# S205D.net
KiCad netlist of a schematic drawn in EAGLE
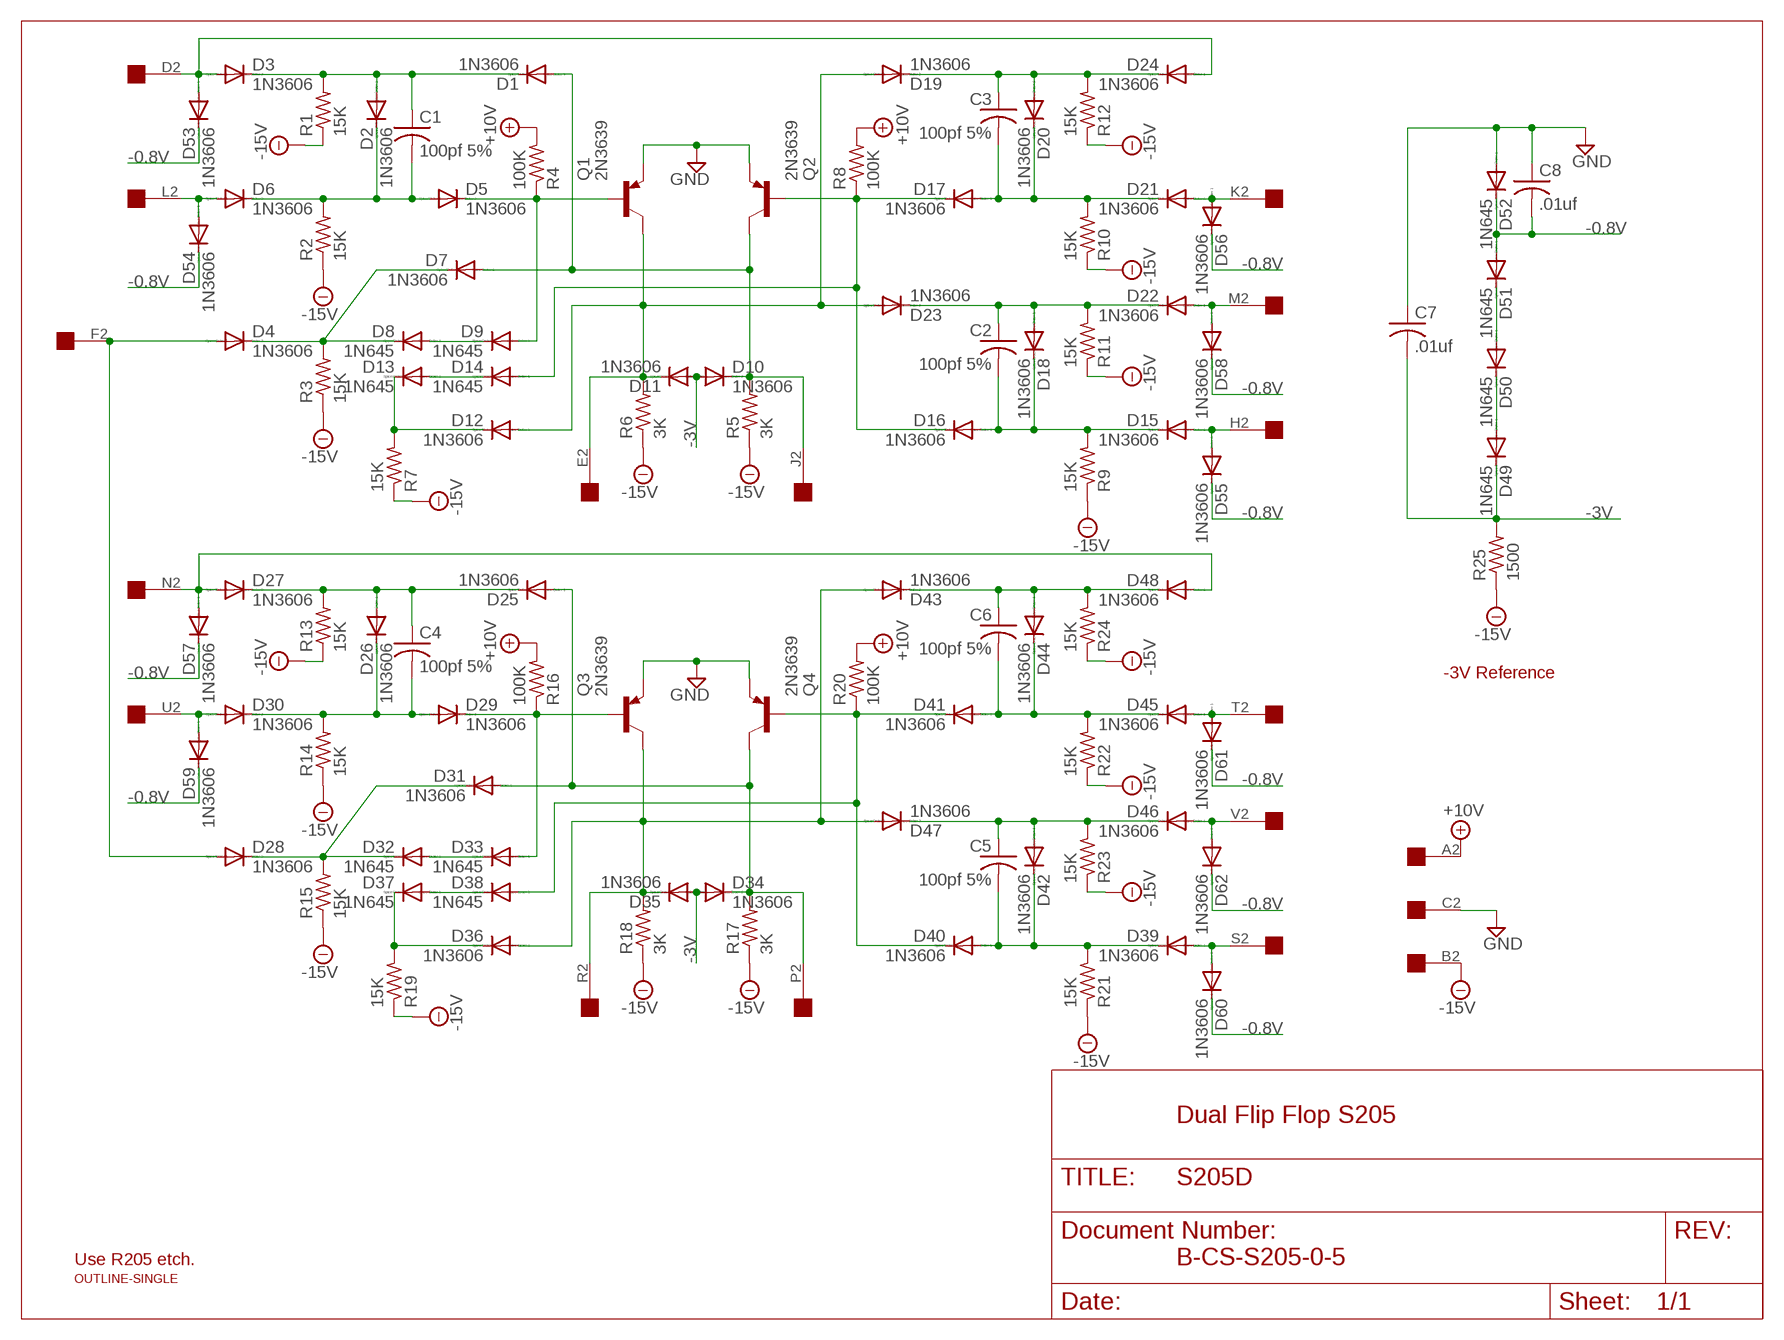
[diagram p0: schematic, sheet 1]

(export (version "E")
  (design (tool "Eeschema 10.0.6"))
  (components
    (comp (ref "C1")
      (value "100pf 5%")
      (footprint "eagle-import:C050-025X075")
      (libsource (lib "eagle-import") (part "C-US050-025X075"))
    )
    (comp (ref "C2")
      (value "100pf 5%")
      (footprint "eagle-import:C050-025X075")
      (libsource (lib "eagle-import") (part "C-US050-025X075"))
    )
    (comp (ref "C3")
      (value "100pf 5%")
      (footprint "eagle-import:C050-025X075")
      (libsource (lib "eagle-import") (part "C-US050-025X075"))
    )
    (comp (ref "C4")
      (value "100pf 5%")
      (footprint "eagle-import:C050-025X075")
      (libsource (lib "eagle-import") (part "C-US050-025X075"))
    )
    (comp (ref "C5")
      (value "100pf 5%")
      (footprint "eagle-import:C050-025X075")
      (libsource (lib "eagle-import") (part "C-US050-025X075"))
    )
    (comp (ref "C6")
      (value "100pf 5%")
      (footprint "eagle-import:C050-025X075")
      (libsource (lib "eagle-import") (part "C-US050-025X075"))
    )
    (comp (ref "C7")
      (value ".01uf")
      (footprint "eagle-import:C050-025X075")
      (libsource (lib "eagle-import") (part "C-US050-025X075"))
    )
    (comp (ref "C8")
      (value ".01uf")
      (footprint "eagle-import:C050-025X075")
      (libsource (lib "eagle-import") (part "C-US050-025X075"))
    )
    (comp (ref "D1")
      (value "1N3606")
      (footprint "eagle-import:DO35-10")
      (libsource (lib "eagle-import") (part "1N4148DO35-10"))
    )
    (comp (ref "D2")
      (value "1N3606")
      (footprint "eagle-import:DO35-10")
      (libsource (lib "eagle-import") (part "1N4148DO35-10"))
    )
    (comp (ref "D3")
      (value "1N3606")
      (footprint "eagle-import:DO35-10")
      (libsource (lib "eagle-import") (part "1N4148DO35-10"))
    )
    (comp (ref "D4")
      (value "1N3606")
      (footprint "eagle-import:DO35-10")
      (libsource (lib "eagle-import") (part "1N4148DO35-10"))
    )
    (comp (ref "D5")
      (value "1N3606")
      (footprint "eagle-import:DO35-10")
      (libsource (lib "eagle-import") (part "1N4148DO35-10"))
    )
    (comp (ref "D6")
      (value "1N3606")
      (footprint "eagle-import:DO35-10")
      (libsource (lib "eagle-import") (part "1N4148DO35-10"))
    )
    (comp (ref "D7")
      (value "1N3606")
      (footprint "eagle-import:DO35-10")
      (libsource (lib "eagle-import") (part "1N4148DO35-10"))
    )
    (comp (ref "D8")
      (value "1N645")
      (footprint "eagle-import:DO35-10")
      (libsource (lib "eagle-import") (part "1N4148DO35-10"))
    )
    (comp (ref "D9")
      (value "1N645")
      (footprint "eagle-import:DO35-10")
      (libsource (lib "eagle-import") (part "1N4148DO35-10"))
    )
    (comp (ref "D10")
      (value "1N3606")
      (footprint "eagle-import:DO35-10")
      (libsource (lib "eagle-import") (part "1N4148DO35-10"))
    )
    (comp (ref "D11")
      (value "1N3606")
      (footprint "eagle-import:DO35-10")
      (libsource (lib "eagle-import") (part "1N4148DO35-10"))
    )
    (comp (ref "D12")
      (value "1N3606")
      (footprint "eagle-import:DO35-10")
      (libsource (lib "eagle-import") (part "1N4148DO35-10"))
    )
    (comp (ref "D13")
      (value "1N645")
      (footprint "eagle-import:DO35-10")
      (libsource (lib "eagle-import") (part "1N4148DO35-10"))
    )
    (comp (ref "D14")
      (value "1N645")
      (footprint "eagle-import:DO35-10")
      (libsource (lib "eagle-import") (part "1N4148DO35-10"))
    )
    (comp (ref "D15")
      (value "1N3606")
      (footprint "eagle-import:DO35-10")
      (libsource (lib "eagle-import") (part "1N4148DO35-10"))
    )
    (comp (ref "D16")
      (value "1N3606")
      (footprint "eagle-import:DO35-10")
      (libsource (lib "eagle-import") (part "1N4148DO35-10"))
    )
    (comp (ref "D17")
      (value "1N3606")
      (footprint "eagle-import:DO35-10")
      (libsource (lib "eagle-import") (part "1N4148DO35-10"))
    )
    (comp (ref "D18")
      (value "1N3606")
      (footprint "eagle-import:DO35-10")
      (libsource (lib "eagle-import") (part "1N4148DO35-10"))
    )
    (comp (ref "D19")
      (value "1N3606")
      (footprint "eagle-import:DO35-10")
      (libsource (lib "eagle-import") (part "1N4148DO35-10"))
    )
    (comp (ref "D20")
      (value "1N3606")
      (footprint "eagle-import:DO35-10")
      (libsource (lib "eagle-import") (part "1N4148DO35-10"))
    )
    (comp (ref "D21")
      (value "1N3606")
      (footprint "eagle-import:DO35-10")
      (libsource (lib "eagle-import") (part "1N4148DO35-10"))
    )
    (comp (ref "D22")
      (value "1N3606")
      (footprint "eagle-import:DO35-10")
      (libsource (lib "eagle-import") (part "1N4148DO35-10"))
    )
    (comp (ref "D23")
      (value "1N3606")
      (footprint "eagle-import:DO35-10")
      (libsource (lib "eagle-import") (part "1N4148DO35-10"))
    )
    (comp (ref "D24")
      (value "1N3606")
      (footprint "eagle-import:DO35-10")
      (libsource (lib "eagle-import") (part "1N4148DO35-10"))
    )
    (comp (ref "D25")
      (value "1N3606")
      (footprint "eagle-import:DO35-10")
      (libsource (lib "eagle-import") (part "1N4148DO35-10"))
    )
    (comp (ref "D26")
      (value "1N3606")
      (footprint "eagle-import:DO35-10")
      (libsource (lib "eagle-import") (part "1N4148DO35-10"))
    )
    (comp (ref "D27")
      (value "1N3606")
      (footprint "eagle-import:DO35-10")
      (libsource (lib "eagle-import") (part "1N4148DO35-10"))
    )
    (comp (ref "D28")
      (value "1N3606")
      (footprint "eagle-import:DO35-10")
      (libsource (lib "eagle-import") (part "1N4148DO35-10"))
    )
    (comp (ref "D29")
      (value "1N3606")
      (footprint "eagle-import:DO35-10")
      (libsource (lib "eagle-import") (part "1N4148DO35-10"))
    )
    (comp (ref "D30")
      (value "1N3606")
      (footprint "eagle-import:DO35-10")
      (libsource (lib "eagle-import") (part "1N4148DO35-10"))
    )
    (comp (ref "D31")
      (value "1N3606")
      (footprint "eagle-import:DO35-10")
      (libsource (lib "eagle-import") (part "1N4148DO35-10"))
    )
    (comp (ref "D32")
      (value "1N645")
      (footprint "eagle-import:DO35-10")
      (libsource (lib "eagle-import") (part "1N4148DO35-10"))
    )
    (comp (ref "D33")
      (value "1N645")
      (footprint "eagle-import:DO35-10")
      (libsource (lib "eagle-import") (part "1N4148DO35-10"))
    )
    (comp (ref "D34")
      (value "1N3606")
      (footprint "eagle-import:DO35-10")
      (libsource (lib "eagle-import") (part "1N4148DO35-10"))
    )
    (comp (ref "D35")
      (value "1N3606")
      (footprint "eagle-import:DO35-10")
      (libsource (lib "eagle-import") (part "1N4148DO35-10"))
    )
    (comp (ref "D36")
      (value "1N3606")
      (footprint "eagle-import:DO35-10")
      (libsource (lib "eagle-import") (part "1N4148DO35-10"))
    )
    (comp (ref "D37")
      (value "1N645")
      (footprint "eagle-import:DO35-10")
      (libsource (lib "eagle-import") (part "1N4148DO35-10"))
    )
    (comp (ref "D38")
      (value "1N645")
      (footprint "eagle-import:DO35-10")
      (libsource (lib "eagle-import") (part "1N4148DO35-10"))
    )
    (comp (ref "D39")
      (value "1N3606")
      (footprint "eagle-import:DO35-10")
      (libsource (lib "eagle-import") (part "1N4148DO35-10"))
    )
    (comp (ref "D40")
      (value "1N3606")
      (footprint "eagle-import:DO35-10")
      (libsource (lib "eagle-import") (part "1N4148DO35-10"))
    )
    (comp (ref "D41")
      (value "1N3606")
      (footprint "eagle-import:DO35-10")
      (libsource (lib "eagle-import") (part "1N4148DO35-10"))
    )
    (comp (ref "D42")
      (value "1N3606")
      (footprint "eagle-import:DO35-10")
      (libsource (lib "eagle-import") (part "1N4148DO35-10"))
    )
    (comp (ref "D43")
      (value "1N3606")
      (footprint "eagle-import:DO35-10")
      (libsource (lib "eagle-import") (part "1N4148DO35-10"))
    )
    (comp (ref "D44")
      (value "1N3606")
      (footprint "eagle-import:DO35-10")
      (libsource (lib "eagle-import") (part "1N4148DO35-10"))
    )
    (comp (ref "D45")
      (value "1N3606")
      (footprint "eagle-import:DO35-10")
      (libsource (lib "eagle-import") (part "1N4148DO35-10"))
    )
    (comp (ref "D46")
      (value "1N3606")
      (footprint "eagle-import:DO35-10")
      (libsource (lib "eagle-import") (part "1N4148DO35-10"))
    )
    (comp (ref "D47")
      (value "1N3606")
      (footprint "eagle-import:DO35-10")
      (libsource (lib "eagle-import") (part "1N4148DO35-10"))
    )
    (comp (ref "D48")
      (value "1N3606")
      (footprint "eagle-import:DO35-10")
      (libsource (lib "eagle-import") (part "1N4148DO35-10"))
    )
    (comp (ref "D49")
      (value "1N645")
      (footprint "eagle-import:DO35-10")
      (libsource (lib "eagle-import") (part "1N4148DO35-10"))
    )
    (comp (ref "D50")
      (value "1N645")
      (footprint "eagle-import:DO35-10")
      (libsource (lib "eagle-import") (part "1N4148DO35-10"))
    )
    (comp (ref "D51")
      (value "1N645")
      (footprint "eagle-import:DO35-10")
      (libsource (lib "eagle-import") (part "1N4148DO35-10"))
    )
    (comp (ref "D52")
      (value "1N645")
      (footprint "eagle-import:DO35-10")
      (libsource (lib "eagle-import") (part "1N4148DO35-10"))
    )
    (comp (ref "D53")
      (value "1N3606")
      (footprint "eagle-import:DO35-10")
      (libsource (lib "eagle-import") (part "1N4148DO35-10"))
    )
    (comp (ref "D54")
      (value "1N3606")
      (footprint "eagle-import:DO35-10")
      (libsource (lib "eagle-import") (part "1N4148DO35-10"))
    )
    (comp (ref "D55")
      (value "1N3606")
      (footprint "eagle-import:DO35-10")
      (libsource (lib "eagle-import") (part "1N4148DO35-10"))
    )
    (comp (ref "D56")
      (value "1N3606")
      (footprint "eagle-import:DO35-10")
      (libsource (lib "eagle-import") (part "1N4148DO35-10"))
    )
    (comp (ref "D57")
      (value "1N3606")
      (footprint "eagle-import:DO35-10")
      (libsource (lib "eagle-import") (part "1N4148DO35-10"))
    )
    (comp (ref "D58")
      (value "1N3606")
      (footprint "eagle-import:DO35-10")
      (libsource (lib "eagle-import") (part "1N4148DO35-10"))
    )
    (comp (ref "D59")
      (value "1N3606")
      (footprint "eagle-import:DO35-10")
      (libsource (lib "eagle-import") (part "1N4148DO35-10"))
    )
    (comp (ref "D60")
      (value "1N3606")
      (footprint "eagle-import:DO35-10")
      (libsource (lib "eagle-import") (part "1N4148DO35-10"))
    )
    (comp (ref "D61")
      (value "1N3606")
      (footprint "eagle-import:DO35-10")
      (libsource (lib "eagle-import") (part "1N4148DO35-10"))
    )
    (comp (ref "D62")
      (value "1N3606")
      (footprint "eagle-import:DO35-10")
      (libsource (lib "eagle-import") (part "1N4148DO35-10"))
    )
    (comp (ref "Q1")
      (value "2N3639")
      (footprint "eagle-import:TO39")
      (libsource (lib "eagle-import") (part "2N3637"))
    )
    (comp (ref "Q2")
      (value "2N3639")
      (footprint "eagle-import:TO39")
      (libsource (lib "eagle-import") (part "2N3637"))
    )
    (comp (ref "Q3")
      (value "2N3639")
      (footprint "eagle-import:TO39")
      (libsource (lib "eagle-import") (part "2N3637"))
    )
    (comp (ref "Q4")
      (value "2N3639")
      (footprint "eagle-import:TO39")
      (libsource (lib "eagle-import") (part "2N3637"))
    )
    (comp (ref "R1")
      (value "15K")
      (footprint "eagle-import:0207_10")
      (libsource (lib "eagle-import") (part "R-US_0207/10"))
    )
    (comp (ref "R2")
      (value "15K")
      (footprint "eagle-import:0207_10")
      (libsource (lib "eagle-import") (part "R-US_0207/10"))
    )
    (comp (ref "R3")
      (value "15K")
      (footprint "eagle-import:0207_10")
      (libsource (lib "eagle-import") (part "R-US_0207/10"))
    )
    (comp (ref "R4")
      (value "100K")
      (footprint "eagle-import:0207_10")
      (libsource (lib "eagle-import") (part "R-US_0207/10"))
    )
    (comp (ref "R5")
      (value "3K")
      (footprint "eagle-import:0207_10")
      (libsource (lib "eagle-import") (part "R-US_0207/10"))
    )
    (comp (ref "R6")
      (value "3K")
      (footprint "eagle-import:0207_10")
      (libsource (lib "eagle-import") (part "R-US_0207/10"))
    )
    (comp (ref "R7")
      (value "15K")
      (footprint "eagle-import:0207_10")
      (libsource (lib "eagle-import") (part "R-US_0207/10"))
    )
    (comp (ref "R8")
      (value "100K")
      (footprint "eagle-import:0207_10")
      (libsource (lib "eagle-import") (part "R-US_0207/10"))
    )
    (comp (ref "R9")
      (value "15K")
      (footprint "eagle-import:0207_10")
      (libsource (lib "eagle-import") (part "R-US_0207/10"))
    )
    (comp (ref "R10")
      (value "15K")
      (footprint "eagle-import:0207_10")
      (libsource (lib "eagle-import") (part "R-US_0207/10"))
    )
    (comp (ref "R11")
      (value "15K")
      (footprint "eagle-import:0207_10")
      (libsource (lib "eagle-import") (part "R-US_0207/10"))
    )
    (comp (ref "R12")
      (value "15K")
      (footprint "eagle-import:0207_10")
      (libsource (lib "eagle-import") (part "R-US_0207/10"))
    )
    (comp (ref "R13")
      (value "15K")
      (footprint "eagle-import:0207_10")
      (libsource (lib "eagle-import") (part "R-US_0207/10"))
    )
    (comp (ref "R14")
      (value "15K")
      (footprint "eagle-import:0207_10")
      (libsource (lib "eagle-import") (part "R-US_0207/10"))
    )
    (comp (ref "R15")
      (value "15K")
      (footprint "eagle-import:0207_10")
      (libsource (lib "eagle-import") (part "R-US_0207/10"))
    )
    (comp (ref "R16")
      (value "100K")
      (footprint "eagle-import:0207_10")
      (libsource (lib "eagle-import") (part "R-US_0207/10"))
    )
    (comp (ref "R17")
      (value "3K")
      (footprint "eagle-import:0207_10")
      (libsource (lib "eagle-import") (part "R-US_0207/10"))
    )
    (comp (ref "R18")
      (value "3K")
      (footprint "eagle-import:0207_10")
      (libsource (lib "eagle-import") (part "R-US_0207/10"))
    )
    (comp (ref "R19")
      (value "15K")
      (footprint "eagle-import:0207_10")
      (libsource (lib "eagle-import") (part "R-US_0207/10"))
    )
    (comp (ref "R20")
      (value "100K")
      (footprint "eagle-import:0207_10")
      (libsource (lib "eagle-import") (part "R-US_0207/10"))
    )
    (comp (ref "R21")
      (value "15K")
      (footprint "eagle-import:0207_10")
      (libsource (lib "eagle-import") (part "R-US_0207/10"))
    )
    (comp (ref "R22")
      (value "15K")
      (footprint "eagle-import:0207_10")
      (libsource (lib "eagle-import") (part "R-US_0207/10"))
    )
    (comp (ref "R23")
      (value "15K")
      (footprint "eagle-import:0207_10")
      (libsource (lib "eagle-import") (part "R-US_0207/10"))
    )
    (comp (ref "R24")
      (value "15K")
      (footprint "eagle-import:0207_10")
      (libsource (lib "eagle-import") (part "R-US_0207/10"))
    )
    (comp (ref "R25")
      (value "1500")
      (footprint "eagle-import:0207_10")
      (libsource (lib "eagle-import") (part "R-US_0207/10"))
    )
    (comp (ref "U$1")
      (value "OUTLINE-SINGLE")
      (footprint "eagle-import:SINGLE")
      (libsource (lib "eagle-import") (part "OUTLINE-SINGLE"))
    )
    (comp (ref "U$2")
      (value "EDGE-1")
      (footprint "eagle-import:EDGE-CON1")
      (libsource (lib "eagle-import") (part "EDGE-1"))
    )
  )
  (nets
    (net (code "1") (name "+10V") (class "Default")
      (node (ref "R16") (pin "2") (pinfunction "2_2") (pintype "passive"))
      (node (ref "R20") (pin "2") (pinfunction "2_2") (pintype "passive"))
      (node (ref "R4") (pin "2") (pinfunction "2_2") (pintype "passive"))
      (node (ref "R8") (pin "2") (pinfunction "2_2") (pintype "passive"))
      (node (ref "U$2") (pin "A2") (pinfunction "1_A2") (pintype "bidirectional"))
    )
    (net (code "2") (name "-15V") (class "Default")
      (node (ref "R1") (pin "1") (pinfunction "1_1") (pintype "passive"))
      (node (ref "R10") (pin "1") (pinfunction "1_1") (pintype "passive"))
      (node (ref "R11") (pin "1") (pinfunction "1_1") (pintype "passive"))
      (node (ref "R12") (pin "1") (pinfunction "1_1") (pintype "passive"))
      (node (ref "R13") (pin "1") (pinfunction "1_1") (pintype "passive"))
      (node (ref "R14") (pin "1") (pinfunction "1_1") (pintype "passive"))
      (node (ref "R15") (pin "1") (pinfunction "1_1") (pintype "passive"))
      (node (ref "R17") (pin "1") (pinfunction "1_1") (pintype "passive"))
      (node (ref "R18") (pin "1") (pinfunction "1_1") (pintype "passive"))
      (node (ref "R19") (pin "1") (pinfunction "1_1") (pintype "passive"))
      (node (ref "R2") (pin "1") (pinfunction "1_1") (pintype "passive"))
      (node (ref "R21") (pin "1") (pinfunction "1_1") (pintype "passive"))
      (node (ref "R22") (pin "1") (pinfunction "1_1") (pintype "passive"))
      (node (ref "R23") (pin "1") (pinfunction "1_1") (pintype "passive"))
      (node (ref "R24") (pin "1") (pinfunction "1_1") (pintype "passive"))
      (node (ref "R25") (pin "1") (pinfunction "1_1") (pintype "passive"))
      (node (ref "R3") (pin "1") (pinfunction "1_1") (pintype "passive"))
      (node (ref "R5") (pin "1") (pinfunction "1_1") (pintype "passive"))
      (node (ref "R6") (pin "1") (pinfunction "1_1") (pintype "passive"))
      (node (ref "R7") (pin "1") (pinfunction "1_1") (pintype "passive"))
      (node (ref "R9") (pin "1") (pinfunction "1_1") (pintype "passive"))
      (node (ref "U$2") (pin "B2") (pinfunction "1_B2") (pintype "bidirectional"))
    )
    (net (code "3") (name "/-0.8V") (class "Default")
      (node (ref "C8") (pin "2") (pinfunction "2_2") (pintype "passive"))
      (node (ref "D51") (pin "A") (pinfunction "A_A") (pintype "passive"))
      (node (ref "D52") (pin "C") (pinfunction "C_C") (pintype "passive"))
      (node (ref "D53") (pin "C") (pinfunction "C_C") (pintype "passive"))
      (node (ref "D54") (pin "C") (pinfunction "C_C") (pintype "passive"))
      (node (ref "D55") (pin "C") (pinfunction "C_C") (pintype "passive"))
      (node (ref "D56") (pin "C") (pinfunction "C_C") (pintype "passive"))
      (node (ref "D57") (pin "C") (pinfunction "C_C") (pintype "passive"))
      (node (ref "D58") (pin "C") (pinfunction "C_C") (pintype "passive"))
      (node (ref "D59") (pin "C") (pinfunction "C_C") (pintype "passive"))
      (node (ref "D60") (pin "C") (pinfunction "C_C") (pintype "passive"))
      (node (ref "D61") (pin "C") (pinfunction "C_C") (pintype "passive"))
      (node (ref "D62") (pin "C") (pinfunction "C_C") (pintype "passive"))
    )
    (net (code "4") (name "/-3V") (class "Default")
      (node (ref "C7") (pin "2") (pinfunction "2_2") (pintype "passive"))
      (node (ref "D10") (pin "A") (pinfunction "A_A") (pintype "passive"))
      (node (ref "D11") (pin "A") (pinfunction "A_A") (pintype "passive"))
      (node (ref "D34") (pin "A") (pinfunction "A_A") (pintype "passive"))
      (node (ref "D35") (pin "A") (pinfunction "A_A") (pintype "passive"))
      (node (ref "D49") (pin "C") (pinfunction "C_C") (pintype "passive"))
      (node (ref "R25") (pin "2") (pinfunction "2_2") (pintype "passive"))
    )
    (net (code "5") (name "GND") (class "Default")
      (node (ref "C7") (pin "1") (pinfunction "1_1") (pintype "passive"))
      (node (ref "C8") (pin "1") (pinfunction "1_1") (pintype "passive"))
      (node (ref "D52") (pin "A") (pinfunction "A_A") (pintype "passive"))
      (node (ref "Q1") (pin "1") (pinfunction "E_1") (pintype "passive"))
      (node (ref "Q2") (pin "1") (pinfunction "E_1") (pintype "passive"))
      (node (ref "Q3") (pin "1") (pinfunction "E_1") (pintype "passive"))
      (node (ref "Q4") (pin "1") (pinfunction "E_1") (pintype "passive"))
      (node (ref "U$2") (pin "C2") (pinfunction "1_C2") (pintype "bidirectional"))
    )
    (net (code "6") (name "Net-(C1-Pad1)") (class "Default")
      (node (ref "C1") (pin "1") (pinfunction "1_1") (pintype "passive"))
      (node (ref "D1") (pin "C") (pinfunction "C_C") (pintype "passive"))
      (node (ref "D2") (pin "A") (pinfunction "A_A") (pintype "passive"))
      (node (ref "D3") (pin "C") (pinfunction "C_C") (pintype "passive"))
      (node (ref "R1") (pin "2") (pinfunction "2_2") (pintype "passive"))
    )
    (net (code "7") (name "Net-(C1-Pad2)") (class "Default")
      (node (ref "C1") (pin "2") (pinfunction "2_2") (pintype "passive"))
      (node (ref "D2") (pin "C") (pinfunction "C_C") (pintype "passive"))
      (node (ref "D5") (pin "A") (pinfunction "A_A") (pintype "passive"))
      (node (ref "D6") (pin "C") (pinfunction "C_C") (pintype "passive"))
      (node (ref "R2") (pin "2") (pinfunction "2_2") (pintype "passive"))
    )
    (net (code "8") (name "Net-(C2-Pad1)") (class "Default")
      (node (ref "C2") (pin "1") (pinfunction "1_1") (pintype "passive"))
      (node (ref "D18") (pin "A") (pinfunction "A_A") (pintype "passive"))
      (node (ref "D22") (pin "C") (pinfunction "C_C") (pintype "passive"))
      (node (ref "D23") (pin "C") (pinfunction "C_C") (pintype "passive"))
      (node (ref "R11") (pin "2") (pinfunction "2_2") (pintype "passive"))
    )
    (net (code "9") (name "Net-(C2-Pad2)") (class "Default")
      (node (ref "C2") (pin "2") (pinfunction "2_2") (pintype "passive"))
      (node (ref "D15") (pin "C") (pinfunction "C_C") (pintype "passive"))
      (node (ref "D16") (pin "A") (pinfunction "A_A") (pintype "passive"))
      (node (ref "D18") (pin "C") (pinfunction "C_C") (pintype "passive"))
      (node (ref "R9") (pin "2") (pinfunction "2_2") (pintype "passive"))
    )
    (net (code "10") (name "Net-(C3-Pad1)") (class "Default")
      (node (ref "C3") (pin "1") (pinfunction "1_1") (pintype "passive"))
      (node (ref "D19") (pin "C") (pinfunction "C_C") (pintype "passive"))
      (node (ref "D20") (pin "A") (pinfunction "A_A") (pintype "passive"))
      (node (ref "D24") (pin "C") (pinfunction "C_C") (pintype "passive"))
      (node (ref "R12") (pin "2") (pinfunction "2_2") (pintype "passive"))
    )
    (net (code "11") (name "Net-(C3-Pad2)") (class "Default")
      (node (ref "C3") (pin "2") (pinfunction "2_2") (pintype "passive"))
      (node (ref "D17") (pin "A") (pinfunction "A_A") (pintype "passive"))
      (node (ref "D20") (pin "C") (pinfunction "C_C") (pintype "passive"))
      (node (ref "D21") (pin "C") (pinfunction "C_C") (pintype "passive"))
      (node (ref "R10") (pin "2") (pinfunction "2_2") (pintype "passive"))
    )
    (net (code "12") (name "Net-(C4-Pad1)") (class "Default")
      (node (ref "C4") (pin "1") (pinfunction "1_1") (pintype "passive"))
      (node (ref "D25") (pin "C") (pinfunction "C_C") (pintype "passive"))
      (node (ref "D26") (pin "A") (pinfunction "A_A") (pintype "passive"))
      (node (ref "D27") (pin "C") (pinfunction "C_C") (pintype "passive"))
      (node (ref "R13") (pin "2") (pinfunction "2_2") (pintype "passive"))
    )
    (net (code "13") (name "Net-(C4-Pad2)") (class "Default")
      (node (ref "C4") (pin "2") (pinfunction "2_2") (pintype "passive"))
      (node (ref "D26") (pin "C") (pinfunction "C_C") (pintype "passive"))
      (node (ref "D29") (pin "A") (pinfunction "A_A") (pintype "passive"))
      (node (ref "D30") (pin "C") (pinfunction "C_C") (pintype "passive"))
      (node (ref "R14") (pin "2") (pinfunction "2_2") (pintype "passive"))
    )
    (net (code "14") (name "Net-(C5-Pad1)") (class "Default")
      (node (ref "C5") (pin "1") (pinfunction "1_1") (pintype "passive"))
      (node (ref "D42") (pin "A") (pinfunction "A_A") (pintype "passive"))
      (node (ref "D46") (pin "C") (pinfunction "C_C") (pintype "passive"))
      (node (ref "D47") (pin "C") (pinfunction "C_C") (pintype "passive"))
      (node (ref "R23") (pin "2") (pinfunction "2_2") (pintype "passive"))
    )
    (net (code "15") (name "Net-(C5-Pad2)") (class "Default")
      (node (ref "C5") (pin "2") (pinfunction "2_2") (pintype "passive"))
      (node (ref "D39") (pin "C") (pinfunction "C_C") (pintype "passive"))
      (node (ref "D40") (pin "A") (pinfunction "A_A") (pintype "passive"))
      (node (ref "D42") (pin "C") (pinfunction "C_C") (pintype "passive"))
      (node (ref "R21") (pin "2") (pinfunction "2_2") (pintype "passive"))
    )
    (net (code "16") (name "Net-(C6-Pad1)") (class "Default")
      (node (ref "C6") (pin "1") (pinfunction "1_1") (pintype "passive"))
      (node (ref "D43") (pin "C") (pinfunction "C_C") (pintype "passive"))
      (node (ref "D44") (pin "A") (pinfunction "A_A") (pintype "passive"))
      (node (ref "D48") (pin "C") (pinfunction "C_C") (pintype "passive"))
      (node (ref "R24") (pin "2") (pinfunction "2_2") (pintype "passive"))
    )
    (net (code "17") (name "Net-(C6-Pad2)") (class "Default")
      (node (ref "C6") (pin "2") (pinfunction "2_2") (pintype "passive"))
      (node (ref "D41") (pin "A") (pinfunction "A_A") (pintype "passive"))
      (node (ref "D44") (pin "C") (pinfunction "C_C") (pintype "passive"))
      (node (ref "D45") (pin "C") (pinfunction "C_C") (pintype "passive"))
      (node (ref "R22") (pin "2") (pinfunction "2_2") (pintype "passive"))
    )
    (net (code "18") (name "Net-(D4-PadC)") (class "Default")
      (node (ref "D4") (pin "C") (pinfunction "C_C") (pintype "passive"))
      (node (ref "D7") (pin "C") (pinfunction "C_C") (pintype "passive"))
      (node (ref "D8") (pin "C") (pinfunction "C_C") (pintype "passive"))
      (node (ref "R3") (pin "2") (pinfunction "2_2") (pintype "passive"))
    )
    (net (code "19") (name "Net-(D8-PadA)") (class "Default")
      (node (ref "D8") (pin "A") (pinfunction "A_A") (pintype "passive"))
      (node (ref "D9") (pin "C") (pinfunction "C_C") (pintype "passive"))
    )
    (net (code "20") (name "Net-(D12-PadC)") (class "Default")
      (node (ref "D12") (pin "C") (pinfunction "C_C") (pintype "passive"))
      (node (ref "D13") (pin "C") (pinfunction "C_C") (pintype "passive"))
      (node (ref "R7") (pin "2") (pinfunction "2_2") (pintype "passive"))
    )
    (net (code "21") (name "Net-(D13-PadA)") (class "Default")
      (node (ref "D13") (pin "A") (pinfunction "A_A") (pintype "passive"))
      (node (ref "D14") (pin "C") (pinfunction "C_C") (pintype "passive"))
    )
    (net (code "22") (name "Net-(D28-PadC)") (class "Default")
      (node (ref "D28") (pin "C") (pinfunction "C_C") (pintype "passive"))
      (node (ref "D31") (pin "C") (pinfunction "C_C") (pintype "passive"))
      (node (ref "D32") (pin "C") (pinfunction "C_C") (pintype "passive"))
      (node (ref "R15") (pin "2") (pinfunction "2_2") (pintype "passive"))
    )
    (net (code "23") (name "Net-(D32-PadA)") (class "Default")
      (node (ref "D32") (pin "A") (pinfunction "A_A") (pintype "passive"))
      (node (ref "D33") (pin "C") (pinfunction "C_C") (pintype "passive"))
    )
    (net (code "24") (name "Net-(D36-PadC)") (class "Default")
      (node (ref "D36") (pin "C") (pinfunction "C_C") (pintype "passive"))
      (node (ref "D37") (pin "C") (pinfunction "C_C") (pintype "passive"))
      (node (ref "R19") (pin "2") (pinfunction "2_2") (pintype "passive"))
    )
    (net (code "25") (name "Net-(D37-PadA)") (class "Default")
      (node (ref "D37") (pin "A") (pinfunction "A_A") (pintype "passive"))
      (node (ref "D38") (pin "C") (pinfunction "C_C") (pintype "passive"))
    )
    (net (code "26") (name "Net-(D49-PadA)") (class "Default")
      (node (ref "D49") (pin "A") (pinfunction "A_A") (pintype "passive"))
      (node (ref "D50") (pin "C") (pinfunction "C_C") (pintype "passive"))
    )
    (net (code "27") (name "Net-(D50-PadA)") (class "Default")
      (node (ref "D50") (pin "A") (pinfunction "A_A") (pintype "passive"))
      (node (ref "D51") (pin "C") (pinfunction "C_C") (pintype "passive"))
    )
    (net (code "28") (name "Net-(Q1-B)") (class "Default")
      (node (ref "D5") (pin "C") (pinfunction "C_C") (pintype "passive"))
      (node (ref "D9") (pin "A") (pinfunction "A_A") (pintype "passive"))
      (node (ref "Q1") (pin "2") (pinfunction "B_2") (pintype "passive"))
      (node (ref "R4") (pin "1") (pinfunction "1_1") (pintype "passive"))
    )
    (net (code "29") (name "Net-(Q1-C)") (class "Default")
      (node (ref "D11") (pin "C") (pinfunction "C_C") (pintype "passive"))
      (node (ref "D12") (pin "A") (pinfunction "A_A") (pintype "passive"))
      (node (ref "D19") (pin "A") (pinfunction "A_A") (pintype "passive"))
      (node (ref "D23") (pin "A") (pinfunction "A_A") (pintype "passive"))
      (node (ref "Q1") (pin "3") (pinfunction "C_3") (pintype "passive"))
      (node (ref "R6") (pin "2") (pinfunction "2_2") (pintype "passive"))
      (node (ref "U$2") (pin "E2") (pinfunction "1_E2") (pintype "bidirectional"))
    )
    (net (code "30") (name "Net-(Q2-B)") (class "Default")
      (node (ref "D14") (pin "A") (pinfunction "A_A") (pintype "passive"))
      (node (ref "D16") (pin "C") (pinfunction "C_C") (pintype "passive"))
      (node (ref "D17") (pin "C") (pinfunction "C_C") (pintype "passive"))
      (node (ref "Q2") (pin "2") (pinfunction "B_2") (pintype "passive"))
      (node (ref "R8") (pin "1") (pinfunction "1_1") (pintype "passive"))
    )
    (net (code "31") (name "Net-(Q2-C)") (class "Default")
      (node (ref "D1") (pin "A") (pinfunction "A_A") (pintype "passive"))
      (node (ref "D10") (pin "C") (pinfunction "C_C") (pintype "passive"))
      (node (ref "D7") (pin "A") (pinfunction "A_A") (pintype "passive"))
      (node (ref "Q2") (pin "3") (pinfunction "C_3") (pintype "passive"))
      (node (ref "R5") (pin "2") (pinfunction "2_2") (pintype "passive"))
      (node (ref "U$2") (pin "J2") (pinfunction "1_J2") (pintype "bidirectional"))
    )
    (net (code "32") (name "Net-(Q3-B)") (class "Default")
      (node (ref "D29") (pin "C") (pinfunction "C_C") (pintype "passive"))
      (node (ref "D33") (pin "A") (pinfunction "A_A") (pintype "passive"))
      (node (ref "Q3") (pin "2") (pinfunction "B_2") (pintype "passive"))
      (node (ref "R16") (pin "1") (pinfunction "1_1") (pintype "passive"))
    )
    (net (code "33") (name "Net-(Q3-C)") (class "Default")
      (node (ref "D35") (pin "C") (pinfunction "C_C") (pintype "passive"))
      (node (ref "D36") (pin "A") (pinfunction "A_A") (pintype "passive"))
      (node (ref "D43") (pin "A") (pinfunction "A_A") (pintype "passive"))
      (node (ref "D47") (pin "A") (pinfunction "A_A") (pintype "passive"))
      (node (ref "Q3") (pin "3") (pinfunction "C_3") (pintype "passive"))
      (node (ref "R18") (pin "2") (pinfunction "2_2") (pintype "passive"))
      (node (ref "U$2") (pin "R2") (pinfunction "1_R2") (pintype "bidirectional"))
    )
    (net (code "34") (name "Net-(Q4-B)") (class "Default")
      (node (ref "D38") (pin "A") (pinfunction "A_A") (pintype "passive"))
      (node (ref "D40") (pin "C") (pinfunction "C_C") (pintype "passive"))
      (node (ref "D41") (pin "C") (pinfunction "C_C") (pintype "passive"))
      (node (ref "Q4") (pin "2") (pinfunction "B_2") (pintype "passive"))
      (node (ref "R20") (pin "1") (pinfunction "1_1") (pintype "passive"))
    )
    (net (code "35") (name "Net-(Q4-C)") (class "Default")
      (node (ref "D25") (pin "A") (pinfunction "A_A") (pintype "passive"))
      (node (ref "D31") (pin "A") (pinfunction "A_A") (pintype "passive"))
      (node (ref "D34") (pin "C") (pinfunction "C_C") (pintype "passive"))
      (node (ref "Q4") (pin "3") (pinfunction "C_3") (pintype "passive"))
      (node (ref "R17") (pin "2") (pinfunction "2_2") (pintype "passive"))
      (node (ref "U$2") (pin "P2") (pinfunction "1_P2") (pintype "bidirectional"))
    )
    (net (code "36") (name "Net-(U$2D-1)") (class "Default")
      (node (ref "D24") (pin "A") (pinfunction "A_A") (pintype "passive"))
      (node (ref "D3") (pin "A") (pinfunction "A_A") (pintype "passive"))
      (node (ref "D53") (pin "A") (pinfunction "A_A") (pintype "passive"))
      (node (ref "U$2") (pin "D2") (pinfunction "1_D2") (pintype "bidirectional"))
    )
    (net (code "37") (name "Net-(U$2F-1)") (class "Default")
      (node (ref "D28") (pin "A") (pinfunction "A_A") (pintype "passive"))
      (node (ref "D4") (pin "A") (pinfunction "A_A") (pintype "passive"))
      (node (ref "U$2") (pin "F2") (pinfunction "1_F2") (pintype "bidirectional"))
    )
    (net (code "38") (name "Net-(U$2G-1)") (class "Default")
      (node (ref "D15") (pin "A") (pinfunction "A_A") (pintype "passive"))
      (node (ref "D55") (pin "A") (pinfunction "A_A") (pintype "passive"))
      (node (ref "U$2") (pin "H2") (pinfunction "1_H2") (pintype "bidirectional"))
    )
    (net (code "39") (name "Net-(U$2I-1)") (class "Default")
      (node (ref "D21") (pin "A") (pinfunction "A_A") (pintype "passive"))
      (node (ref "D56") (pin "A") (pinfunction "A_A") (pintype "passive"))
      (node (ref "U$2") (pin "K2") (pinfunction "1_K2") (pintype "bidirectional"))
    )
    (net (code "40") (name "Net-(U$2J-1)") (class "Default")
      (node (ref "D54") (pin "A") (pinfunction "A_A") (pintype "passive"))
      (node (ref "D6") (pin "A") (pinfunction "A_A") (pintype "passive"))
      (node (ref "U$2") (pin "L2") (pinfunction "1_L2") (pintype "bidirectional"))
    )
    (net (code "41") (name "Net-(U$2K-1)") (class "Default")
      (node (ref "D22") (pin "A") (pinfunction "A_A") (pintype "passive"))
      (node (ref "D58") (pin "A") (pinfunction "A_A") (pintype "passive"))
      (node (ref "U$2") (pin "M2") (pinfunction "1_M2") (pintype "bidirectional"))
    )
    (net (code "42") (name "Net-(U$2L-1)") (class "Default")
      (node (ref "D27") (pin "A") (pinfunction "A_A") (pintype "passive"))
      (node (ref "D48") (pin "A") (pinfunction "A_A") (pintype "passive"))
      (node (ref "D57") (pin "A") (pinfunction "A_A") (pintype "passive"))
      (node (ref "U$2") (pin "N2") (pinfunction "1_N2") (pintype "bidirectional"))
    )
    (net (code "43") (name "Net-(U$2O-1)") (class "Default")
      (node (ref "D39") (pin "A") (pinfunction "A_A") (pintype "passive"))
      (node (ref "D60") (pin "A") (pinfunction "A_A") (pintype "passive"))
      (node (ref "U$2") (pin "S2") (pinfunction "1_S2") (pintype "bidirectional"))
    )
    (net (code "44") (name "Net-(U$2P-1)") (class "Default")
      (node (ref "D45") (pin "A") (pinfunction "A_A") (pintype "passive"))
      (node (ref "D61") (pin "A") (pinfunction "A_A") (pintype "passive"))
      (node (ref "U$2") (pin "T2") (pinfunction "1_T2") (pintype "bidirectional"))
    )
    (net (code "45") (name "Net-(U$2Q-1)") (class "Default")
      (node (ref "D30") (pin "A") (pinfunction "A_A") (pintype "passive"))
      (node (ref "D59") (pin "A") (pinfunction "A_A") (pintype "passive"))
      (node (ref "U$2") (pin "U2") (pinfunction "1_U2") (pintype "bidirectional"))
    )
    (net (code "46") (name "Net-(U$2R-1)") (class "Default")
      (node (ref "D46") (pin "A") (pinfunction "A_A") (pintype "passive"))
      (node (ref "D62") (pin "A") (pinfunction "A_A") (pintype "passive"))
      (node (ref "U$2") (pin "V2") (pinfunction "1_V2") (pintype "bidirectional"))
    )
  )
)
